# I2C_IO_Expander.net
KiCad netlist of a schematic drawn in Altium Designer
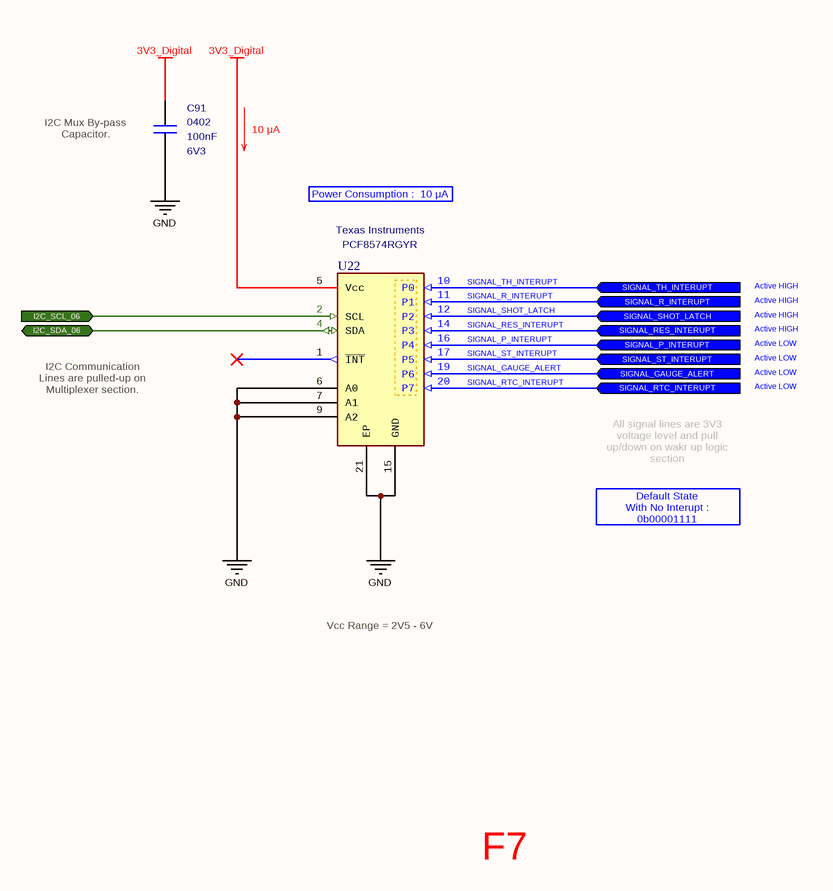
[diagram p0: I2C IO Expander.SchDoc]

(export (version "E")
  (design (tool "Eeschema 10.0.6"))
  (components
    (comp (ref "C91")
      (value "100nF")
      (footprint "CAPACITOR_0402")
      (description "Capacitor - 100nF [0402-6V3] (Ceramic)")
      (fields
        (field (name "MANUFACTURER_PART_NUMBER") "04026D104KAT4A")
        (field (name "MOUSER_PART_NUMBER") "581-04026D104KAT4A")
        (field (name "CASE") "0402")
        (field (name "VOLTAGE") "6V3")
      )
      (libsource (lib "Ovoo_Schematic") (part "Capacitor - 100nF [0402-6V3]"))
    )
    (comp (ref "U22")
      (value "I2C I/O Expander")
      (footprint "VQFN20")
      (description "Interface - I/O Expanders Remote 8-Bit I/O Expander for I2C-Bus")
      (fields
        (field (name "MOUSER_PART_NUMBER") "595-PCF8574RGYR")
        (field (name "MANUFACTURER_PART_NUMBER") "PCF8574RGYR")
        (field (name "MANUFACTURER_NAME") "Texas Instruments")
      )
      (libsource (lib "Ovoo_Schematic") (part "IC - PCF8574RGYR"))
    )
  )
  (nets
    (net (code "1") (name "/I2C_SCL_06") (class "Default")
      (node (ref "U22") (pin "2") (pinfunction "SCL_2") (pintype "input"))
    )
    (net (code "2") (name "/I2C_SDA_06") (class "Default")
      (node (ref "U22") (pin "4") (pinfunction "SDA_4") (pintype "bidirectional"))
    )
    (net (code "3") (name "/SIGNAL_GAUGE_ALERT") (class "Default")
      (node (ref "U22") (pin "19") (pinfunction "P6_19") (pintype "input"))
    )
    (net (code "4") (name "/SIGNAL_P_INTERUPT") (class "Default")
      (node (ref "U22") (pin "16") (pinfunction "P4_16") (pintype "input"))
    )
    (net (code "5") (name "/SIGNAL_RES_INTERUPT") (class "Default")
      (node (ref "U22") (pin "14") (pinfunction "P3_14") (pintype "input"))
    )
    (net (code "6") (name "/SIGNAL_RTC_INTERUPT") (class "Default")
      (node (ref "U22") (pin "20") (pinfunction "P7_20") (pintype "input"))
    )
    (net (code "7") (name "/SIGNAL_R_INTERUPT") (class "Default")
      (node (ref "U22") (pin "11") (pinfunction "P1_11") (pintype "input"))
    )
    (net (code "8") (name "/SIGNAL_SHOT_LATCH") (class "Default")
      (node (ref "U22") (pin "12") (pinfunction "P2_12") (pintype "input"))
    )
    (net (code "9") (name "/SIGNAL_ST_INTERUPT") (class "Default")
      (node (ref "U22") (pin "17") (pinfunction "P5_17") (pintype "input"))
    )
    (net (code "10") (name "/SIGNAL_TH_INTERUPT") (class "Default")
      (node (ref "U22") (pin "10") (pinfunction "P0_10") (pintype "input"))
    )
    (net (code "11") (name "3V3_Digital") (class "Default")
      (node (ref "C91") (pin "2") (pinfunction "2_2") (pintype "passive"))
      (node (ref "U22") (pin "5") (pinfunction "Vcc_5") (pintype "power_in"))
    )
    (net (code "12") (name "GND") (class "Default")
      (node (ref "C91") (pin "1") (pinfunction "1_1") (pintype "passive"))
      (node (ref "U22") (pin "15") (pinfunction "GND_15") (pintype "power_in"))
      (node (ref "U22") (pin "21") (pinfunction "EP_21") (pintype "power_in"))
      (node (ref "U22") (pin "6") (pinfunction "A0_6") (pintype "passive"))
      (node (ref "U22") (pin "7") (pinfunction "A1_7") (pintype "passive"))
      (node (ref "U22") (pin "9") (pinfunction "A2_9") (pintype "passive"))
    )
    (net (code "13") (name "unconnected-(U22-~{INT}-Pad1)") (class "Default")
      (node (ref "U22") (pin "1") (pinfunction "~{INT}_1") (pintype "output+no_connect"))
    )
  )
)
